# SunS_fixture_EGSE_AVR.net
KiCad netlist of a schematic drawn in Altium Designer
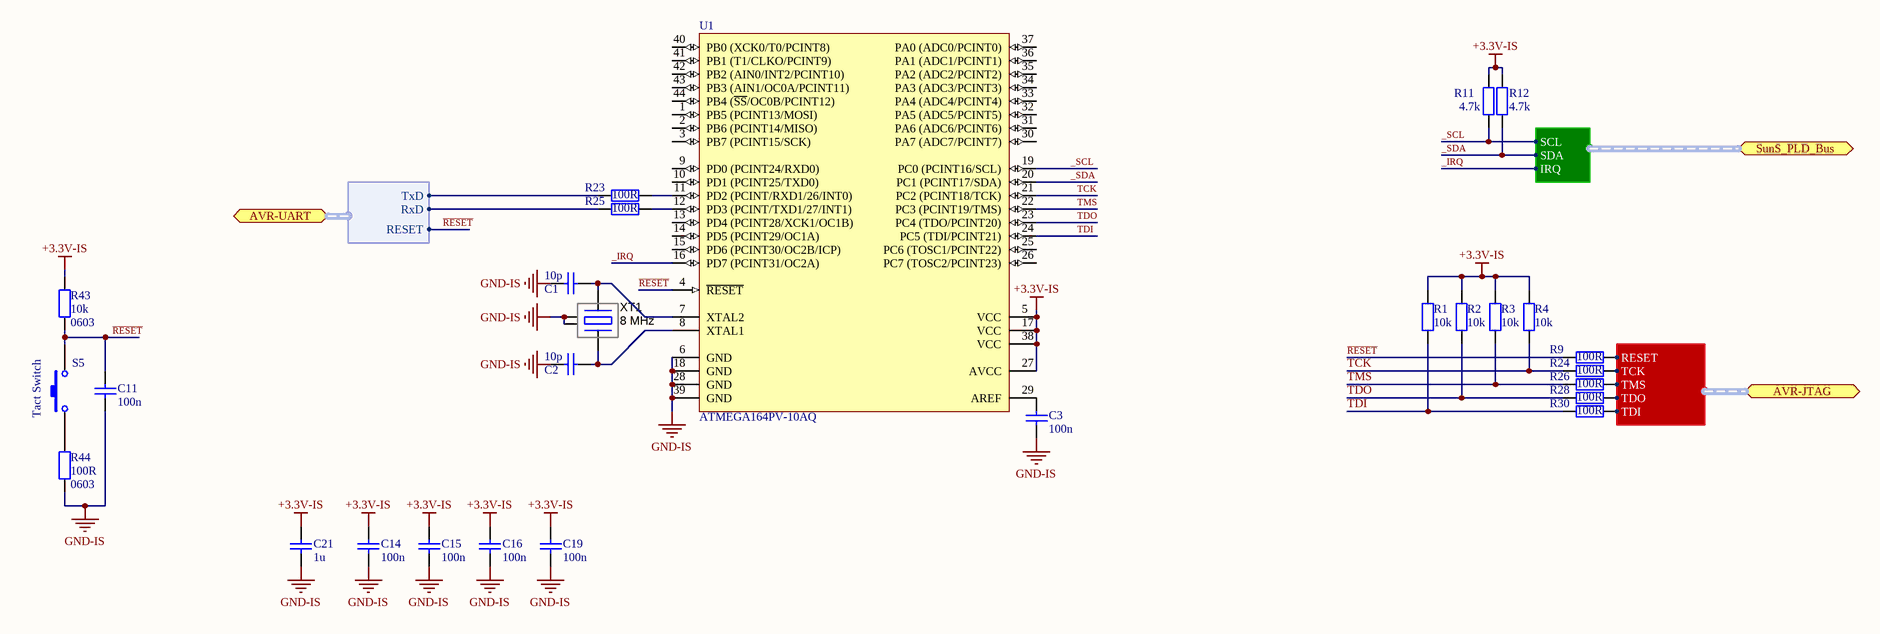
[diagram p0: SunS_fixture_EGSE_AVR.SchDoc]

(export (version "E")
  (design (tool "Eeschema 10.0.6"))
  (components
    (comp (ref "C1")
      (value "10p")
      (footprint "SMD_Capacitor_0603")
      (description "Cap")
      (libsource (lib "capacitors") (part "Cap"))
    )
    (comp (ref "C2")
      (value "10p")
      (footprint "SMD_Capacitor_0603")
      (description "Cap")
      (libsource (lib "capacitors") (part "Cap"))
    )
    (comp (ref "C3")
      (value "100n")
      (footprint "SMD_Capacitor_0603")
      (description "Cap")
      (libsource (lib "capacitors") (part "Cap"))
    )
    (comp (ref "C11")
      (value "100n")
      (footprint "SMD_Capacitor_0603")
      (description "Cap")
      (libsource (lib "capacitors") (part "Cap"))
    )
    (comp (ref "C14")
      (value "100n")
      (footprint "SMD_Capacitor_0603")
      (description "Cap")
      (libsource (lib "capacitors") (part "Cap"))
    )
    (comp (ref "C15")
      (value "100n")
      (footprint "SMD_Capacitor_0603")
      (description "Cap")
      (libsource (lib "capacitors") (part "Cap"))
    )
    (comp (ref "C16")
      (value "100n")
      (footprint "SMD_Capacitor_0603")
      (description "Cap")
      (libsource (lib "capacitors") (part "Cap"))
    )
    (comp (ref "C19")
      (value "100n")
      (footprint "SMD_Capacitor_0603")
      (description "Cap")
      (libsource (lib "capacitors") (part "Cap"))
    )
    (comp (ref "C21")
      (value "1u")
      (footprint "SMD_Capacitor_1206")
      (description "Cap")
      (libsource (lib "capacitors") (part "Cap"))
    )
    (comp (ref "R1") (value "10k") (footprint "SMD_Resistor_0603") (libsource (lib "") (part "Res_2")))
    (comp (ref "R2") (value "10k") (footprint "SMD_Resistor_0603") (libsource (lib "resistors") (part "Res")))
    (comp (ref "R3") (value "10k") (footprint "SMD_Resistor_0603") (libsource (lib "resistors") (part "Res")))
    (comp (ref "R4") (value "10k") (footprint "SMD_Resistor_0603") (libsource (lib "") (part "Res_2")))
    (comp (ref "R9") (value "100R") (footprint "SMD_Resistor_0603") (libsource (lib "") (part "Res_2")))
    (comp (ref "R11") (value "4.7k") (footprint "SMD_Resistor_0603") (libsource (lib "") (part "Res_2")))
    (comp (ref "R12") (value "4.7k") (footprint "SMD_Resistor_0603") (libsource (lib "") (part "Res_3")))
    (comp (ref "R23") (value "100R") (footprint "SMD_Resistor_0603") (libsource (lib "") (part "Res_1")))
    (comp (ref "R24") (value "100R") (footprint "SMD_Resistor_0603") (libsource (lib "") (part "Res_2")))
    (comp (ref "R25") (value "100R") (footprint "SMD_Resistor_0603") (libsource (lib "") (part "Res_1")))
    (comp (ref "R26") (value "100R") (footprint "SMD_Resistor_0603") (libsource (lib "") (part "Res_2")))
    (comp (ref "R28") (value "100R") (footprint "SMD_Resistor_0603") (libsource (lib "") (part "Res_2")))
    (comp (ref "R30") (value "100R") (footprint "SMD_Resistor_0603") (libsource (lib "") (part "Res_2")))
    (comp (ref "R43")
      (value "10k")
      (footprint "SMD_Resistor_0603")
      (fields (field (name "PACKAGE") "0603"))
      (libsource (lib "") (part "Res_2"))
    )
    (comp (ref "R44")
      (value "100R")
      (footprint "SMD_Resistor_0603")
      (fields (field (name "PACKAGE") "0603"))
      (libsource (lib "") (part "Res_2"))
    )
    (comp (ref "S5")
      (value "Tact Switch")
      (footprint "Tact Switch 3x6")
      (libsource (lib "switches") (part "TactSwitch"))
    )
    (comp (ref "U1")
      (value "ATMEGA164PV-10AQ")
      (footprint "TQFP-44")
      (description "General-purpose microcontroller")
      (libsource (lib "microcircuits") (part "ATMEGA164PV-10AQ"))
    )
    (comp (ref "XT1")
      (value "8 MHz")
      (footprint "SMD, 5mm x 3.2mm")
      (description "Resonator Ceramic")
      (fields (field (name "MANUFACTURER PART NUMBER") "ABM3B-8.000MHZ-B2-T"))
      (libsource (lib "crystal") (part "ABM3B-8.000MHZ-B2-T"))
    )
  )
  (nets
    (net (code "4") (name "+3.3V-IS") (class "Default")
      (node (ref "C14") (pin "1") (pinfunction "1_1") (pintype "passive"))
      (node (ref "C15") (pin "1") (pinfunction "1_1") (pintype "passive"))
      (node (ref "C16") (pin "1") (pinfunction "1_1") (pintype "passive"))
      (node (ref "C19") (pin "1") (pinfunction "1_1") (pintype "passive"))
      (node (ref "C21") (pin "1") (pinfunction "1_1") (pintype "passive"))
      (node (ref "R1") (pin "1") (pinfunction "1_1") (pintype "passive"))
      (node (ref "R11") (pin "1") (pinfunction "1_1") (pintype "passive"))
      (node (ref "R12") (pin "1") (pinfunction "1_1") (pintype "passive"))
      (node (ref "R2") (pin "2") (pinfunction "2_2") (pintype "passive"))
      (node (ref "R3") (pin "2") (pinfunction "2_2") (pintype "passive"))
      (node (ref "R4") (pin "1") (pinfunction "1_1") (pintype "passive"))
      (node (ref "R43") (pin "1") (pinfunction "1_1") (pintype "passive"))
      (node (ref "U1") (pin "17") (pinfunction "VCC_17") (pintype "power_in"))
      (node (ref "U1") (pin "27") (pinfunction "AVCC_27") (pintype "power_in"))
      (node (ref "U1") (pin "38") (pinfunction "VCC_38") (pintype "power_in"))
      (node (ref "U1") (pin "5") (pinfunction "VCC_5") (pintype "power_in"))
    )
    (net (code "5") (name "/RxD") (class "Default")
      (node (ref "R25") (pin "1") (pinfunction "1_1") (pintype "passive"))
    )
    (net (code "6") (name "/TCK") (class "Default")
      (node (ref "R24") (pin "2") (pinfunction "2_2") (pintype "passive"))
      (node (ref "R4") (pin "2") (pinfunction "2_2") (pintype "passive"))
      (node (ref "U1") (pin "21") (pinfunction "PC2_(PCINT18/TCK)_21") (pintype "bidirectional"))
    )
    (net (code "7") (name "/TDI") (class "Default")
      (node (ref "R1") (pin "2") (pinfunction "2_2") (pintype "passive"))
      (node (ref "R30") (pin "2") (pinfunction "2_2") (pintype "passive"))
      (node (ref "U1") (pin "24") (pinfunction "PC5_(TDI/PCINT21)_24") (pintype "bidirectional"))
    )
    (net (code "8") (name "/TDO") (class "Default")
      (node (ref "R2") (pin "1") (pinfunction "1_1") (pintype "passive"))
      (node (ref "R28") (pin "2") (pinfunction "2_2") (pintype "passive"))
      (node (ref "U1") (pin "23") (pinfunction "PC4_(TDO/PCINT20)_23") (pintype "bidirectional"))
    )
    (net (code "9") (name "/TMS") (class "Default")
      (node (ref "R26") (pin "2") (pinfunction "2_2") (pintype "passive"))
      (node (ref "R3") (pin "1") (pinfunction "1_1") (pintype "passive"))
      (node (ref "U1") (pin "22") (pinfunction "PC3_(PCINT19/TMS)_22") (pintype "bidirectional"))
    )
    (net (code "10") (name "/TxD") (class "Default")
      (node (ref "R23") (pin "1") (pinfunction "1_1") (pintype "passive"))
    )
    (net (code "11") (name "/_IRQ") (class "Default")
      (node (ref "U1") (pin "16") (pinfunction "PD7_(PCINT31/OC2A)_16") (pintype "bidirectional"))
    )
    (net (code "12") (name "/_SCL") (class "Default")
      (node (ref "R11") (pin "2") (pinfunction "2_2") (pintype "passive"))
      (node (ref "U1") (pin "19") (pinfunction "PC0_(PCINT16/SCL)_19") (pintype "bidirectional"))
    )
    (net (code "13") (name "/_SDA") (class "Default")
      (node (ref "R12") (pin "2") (pinfunction "2_2") (pintype "passive"))
      (node (ref "U1") (pin "20") (pinfunction "PC1_(PCINT17/SDA)_20") (pintype "bidirectional"))
    )
    (net (code "17") (name "/~{RESET}") (class "Default")
      (node (ref "C11") (pin "1") (pinfunction "1_1") (pintype "passive"))
      (node (ref "R43") (pin "2") (pinfunction "2_2") (pintype "passive"))
      (node (ref "R9") (pin "2") (pinfunction "2_2") (pintype "passive"))
      (node (ref "S5") (pin "2") (pinfunction "2_2") (pintype "passive"))
      (node (ref "U1") (pin "4") (pinfunction "~{RESET}_4") (pintype "input"))
    )
    (net (code "18") (name "GND-IS") (class "Default")
      (node (ref "C1") (pin "2") (pinfunction "2_2") (pintype "passive"))
      (node (ref "C11") (pin "2") (pinfunction "2_2") (pintype "passive"))
      (node (ref "C14") (pin "2") (pinfunction "2_2") (pintype "passive"))
      (node (ref "C15") (pin "2") (pinfunction "2_2") (pintype "passive"))
      (node (ref "C16") (pin "2") (pinfunction "2_2") (pintype "passive"))
      (node (ref "C19") (pin "2") (pinfunction "2_2") (pintype "passive"))
      (node (ref "C2") (pin "2") (pinfunction "2_2") (pintype "passive"))
      (node (ref "C21") (pin "2") (pinfunction "2_2") (pintype "passive"))
      (node (ref "C3") (pin "2") (pinfunction "2_2") (pintype "passive"))
      (node (ref "R44") (pin "2") (pinfunction "2_2") (pintype "passive"))
      (node (ref "U1") (pin "18") (pinfunction "GND_18") (pintype "power_in"))
      (node (ref "U1") (pin "28") (pinfunction "GND_28") (pintype "power_in"))
      (node (ref "U1") (pin "39") (pinfunction "GND_39") (pintype "power_in"))
      (node (ref "U1") (pin "6") (pinfunction "GND_6") (pintype "power_in"))
      (node (ref "XT1") (pin "2") (pinfunction "GND_2") (pintype "passive"))
      (node (ref "XT1") (pin "4") (pinfunction "GND_4") (pintype "passive"))
    )
    (net (code "19") (name "Net-(R44-Pad1)") (class "Default")
      (node (ref "R44") (pin "1") (pinfunction "1_1") (pintype "passive"))
      (node (ref "S5") (pin "1") (pinfunction "1_1") (pintype "passive"))
    )
    (net (code "20") (name "Net-(U1-AREF)") (class "Default")
      (node (ref "C3") (pin "1") (pinfunction "1_1") (pintype "passive"))
      (node (ref "U1") (pin "29") (pinfunction "AREF_29") (pintype "power_in"))
    )
    (net (code "21") (name "Net-(U1-PD2_(PCINT{slash}RXD1{slash}26{slash}INT0))") (class "Default")
      (node (ref "R23") (pin "2") (pinfunction "2_2") (pintype "passive"))
      (node (ref "U1") (pin "11") (pinfunction "PD2_(PCINT/RXD1/26/INT0)_11") (pintype "bidirectional"))
    )
    (net (code "22") (name "Net-(U1-PD3_(PCINT{slash}TXD1{slash}27{slash}INT1))") (class "Default")
      (node (ref "R25") (pin "2") (pinfunction "2_2") (pintype "passive"))
      (node (ref "U1") (pin "12") (pinfunction "PD3_(PCINT/TXD1/27/INT1)_12") (pintype "bidirectional"))
    )
    (net (code "23") (name "Net-(U1-XTAL1)") (class "Default")
      (node (ref "C2") (pin "1") (pinfunction "1_1") (pintype "passive"))
      (node (ref "U1") (pin "8") (pinfunction "XTAL1_8") (pintype "passive"))
      (node (ref "XT1") (pin "3") (pinfunction "out_3") (pintype "passive"))
    )
    (net (code "24") (name "Net-(U1-XTAL2)") (class "Default")
      (node (ref "C1") (pin "1") (pinfunction "1_1") (pintype "passive"))
      (node (ref "U1") (pin "7") (pinfunction "XTAL2_7") (pintype "passive"))
      (node (ref "XT1") (pin "1") (pinfunction "inp_1") (pintype "passive"))
    )
    (net (code "25") (name "unconnected-(R9-Pad1)") (class "Default")
      (node (ref "R9") (pin "1") (pinfunction "1_1") (pintype "passive"))
    )
    (net (code "26") (name "unconnected-(R24-Pad1)") (class "Default")
      (node (ref "R24") (pin "1") (pinfunction "1_1") (pintype "passive"))
    )
    (net (code "27") (name "unconnected-(R26-Pad1)") (class "Default")
      (node (ref "R26") (pin "1") (pinfunction "1_1") (pintype "passive"))
    )
    (net (code "28") (name "unconnected-(R28-Pad1)") (class "Default")
      (node (ref "R28") (pin "1") (pinfunction "1_1") (pintype "passive"))
    )
    (net (code "29") (name "unconnected-(R30-Pad1)") (class "Default")
      (node (ref "R30") (pin "1") (pinfunction "1_1") (pintype "passive"))
    )
    (net (code "30") (name "unconnected-(U1-PA0_(ADC0{slash}PCINT0)-Pad37)") (class "Default")
      (node (ref "U1") (pin "37") (pinfunction "PA0_(ADC0/PCINT0)_37") (pintype "bidirectional"))
    )
    (net (code "31") (name "unconnected-(U1-PA1_(ADC1{slash}PCINT1)-Pad36)") (class "Default")
      (node (ref "U1") (pin "36") (pinfunction "PA1_(ADC1/PCINT1)_36") (pintype "bidirectional"))
    )
    (net (code "32") (name "unconnected-(U1-PA2_(ADC2{slash}PCINT2)-Pad35)") (class "Default")
      (node (ref "U1") (pin "35") (pinfunction "PA2_(ADC2/PCINT2)_35") (pintype "bidirectional"))
    )
    (net (code "33") (name "unconnected-(U1-PA3_(ADC3{slash}PCINT3)-Pad34)") (class "Default")
      (node (ref "U1") (pin "34") (pinfunction "PA3_(ADC3/PCINT3)_34") (pintype "bidirectional"))
    )
    (net (code "34") (name "unconnected-(U1-PA4_(ADC4{slash}PCINT4)-Pad33)") (class "Default")
      (node (ref "U1") (pin "33") (pinfunction "PA4_(ADC4/PCINT4)_33") (pintype "bidirectional"))
    )
    (net (code "35") (name "unconnected-(U1-PA5_(ADC5{slash}PCINT5)-Pad32)") (class "Default")
      (node (ref "U1") (pin "32") (pinfunction "PA5_(ADC5/PCINT5)_32") (pintype "bidirectional"))
    )
    (net (code "36") (name "unconnected-(U1-PA6_(ADC6{slash}PCINT6)-Pad31)") (class "Default")
      (node (ref "U1") (pin "31") (pinfunction "PA6_(ADC6/PCINT6)_31") (pintype "bidirectional"))
    )
    (net (code "37") (name "unconnected-(U1-PA7_(ADC7{slash}PCINT7)-Pad30)") (class "Default")
      (node (ref "U1") (pin "30") (pinfunction "PA7_(ADC7/PCINT7)_30") (pintype "bidirectional"))
    )
    (net (code "38") (name "unconnected-(U1-PB0_(XCK0{slash}T0{slash}PCINT8)-Pad40)") (class "Default")
      (node (ref "U1") (pin "40") (pinfunction "PB0_(XCK0/T0/PCINT8)_40") (pintype "bidirectional"))
    )
    (net (code "39") (name "unconnected-(U1-PB1_(T1{slash}CLKO{slash}PCINT9)-Pad41)") (class "Default")
      (node (ref "U1") (pin "41") (pinfunction "PB1_(T1/CLKO/PCINT9)_41") (pintype "bidirectional"))
    )
    (net (code "40") (name "unconnected-(U1-PB2_(AIN0{slash}INT2{slash}PCINT10)-Pad42)") (class "Default")
      (node (ref "U1") (pin "42") (pinfunction "PB2_(AIN0/INT2/PCINT10)_42") (pintype "bidirectional"))
    )
    (net (code "41") (name "unconnected-(U1-PB3_(AIN1{slash}OC0A{slash}PCINT11)-Pad43)") (class "Default")
      (node (ref "U1") (pin "43") (pinfunction "PB3_(AIN1/OC0A/PCINT11)_43") (pintype "bidirectional"))
    )
    (net (code "42") (name "unconnected-(U1-PB4_(~{SS}{slash}OC0B{slash}PCINT12)-Pad44)") (class "Default")
      (node (ref "U1") (pin "44") (pinfunction "PB4_(~{SS}/OC0B/PCINT12)_44") (pintype "bidirectional"))
    )
    (net (code "43") (name "unconnected-(U1-PB5_(PCINT13{slash}MOSI)-Pad1)") (class "Default")
      (node (ref "U1") (pin "1") (pinfunction "PB5_(PCINT13/MOSI)_1") (pintype "bidirectional"))
    )
    (net (code "44") (name "unconnected-(U1-PB6_(PCINT14{slash}MISO)-Pad2)") (class "Default")
      (node (ref "U1") (pin "2") (pinfunction "PB6_(PCINT14/MISO)_2") (pintype "bidirectional"))
    )
    (net (code "45") (name "unconnected-(U1-PB7_(PCINT15{slash}SCK)-Pad3)") (class "Default")
      (node (ref "U1") (pin "3") (pinfunction "PB7_(PCINT15/SCK)_3") (pintype "bidirectional"))
    )
    (net (code "46") (name "unconnected-(U1-PC6_(TOSC1{slash}PCINT22)-Pad25)") (class "Default")
      (node (ref "U1") (pin "25") (pinfunction "PC6_(TOSC1/PCINT22)_25") (pintype "bidirectional"))
    )
    (net (code "47") (name "unconnected-(U1-PC7_(TOSC2{slash}PCINT23)-Pad26)") (class "Default")
      (node (ref "U1") (pin "26") (pinfunction "PC7_(TOSC2/PCINT23)_26") (pintype "bidirectional"))
    )
    (net (code "48") (name "unconnected-(U1-PD0_(PCINT24{slash}RXD0)-Pad9)") (class "Default")
      (node (ref "U1") (pin "9") (pinfunction "PD0_(PCINT24/RXD0)_9") (pintype "bidirectional"))
    )
    (net (code "49") (name "unconnected-(U1-PD1_(PCINT25{slash}TXD0)-Pad10)") (class "Default")
      (node (ref "U1") (pin "10") (pinfunction "PD1_(PCINT25/TXD0)_10") (pintype "bidirectional"))
    )
    (net (code "50") (name "unconnected-(U1-PD4_(PCINT28{slash}XCK1{slash}OC1B)-Pad13)") (class "Default")
      (node (ref "U1") (pin "13") (pinfunction "PD4_(PCINT28/XCK1/OC1B)_13") (pintype "bidirectional"))
    )
    (net (code "51") (name "unconnected-(U1-PD5_(PCINT29{slash}OC1A)-Pad14)") (class "Default")
      (node (ref "U1") (pin "14") (pinfunction "PD5_(PCINT29/OC1A)_14") (pintype "bidirectional"))
    )
    (net (code "52") (name "unconnected-(U1-PD6_(PCINT30{slash}OC2B{slash}ICP)-Pad15)") (class "Default")
      (node (ref "U1") (pin "15") (pinfunction "PD6_(PCINT30/OC2B/ICP)_15") (pintype "bidirectional"))
    )
  )
)
